# Torent_Module_75.net
KiCad netlist of a schematic drawn in EAGLE
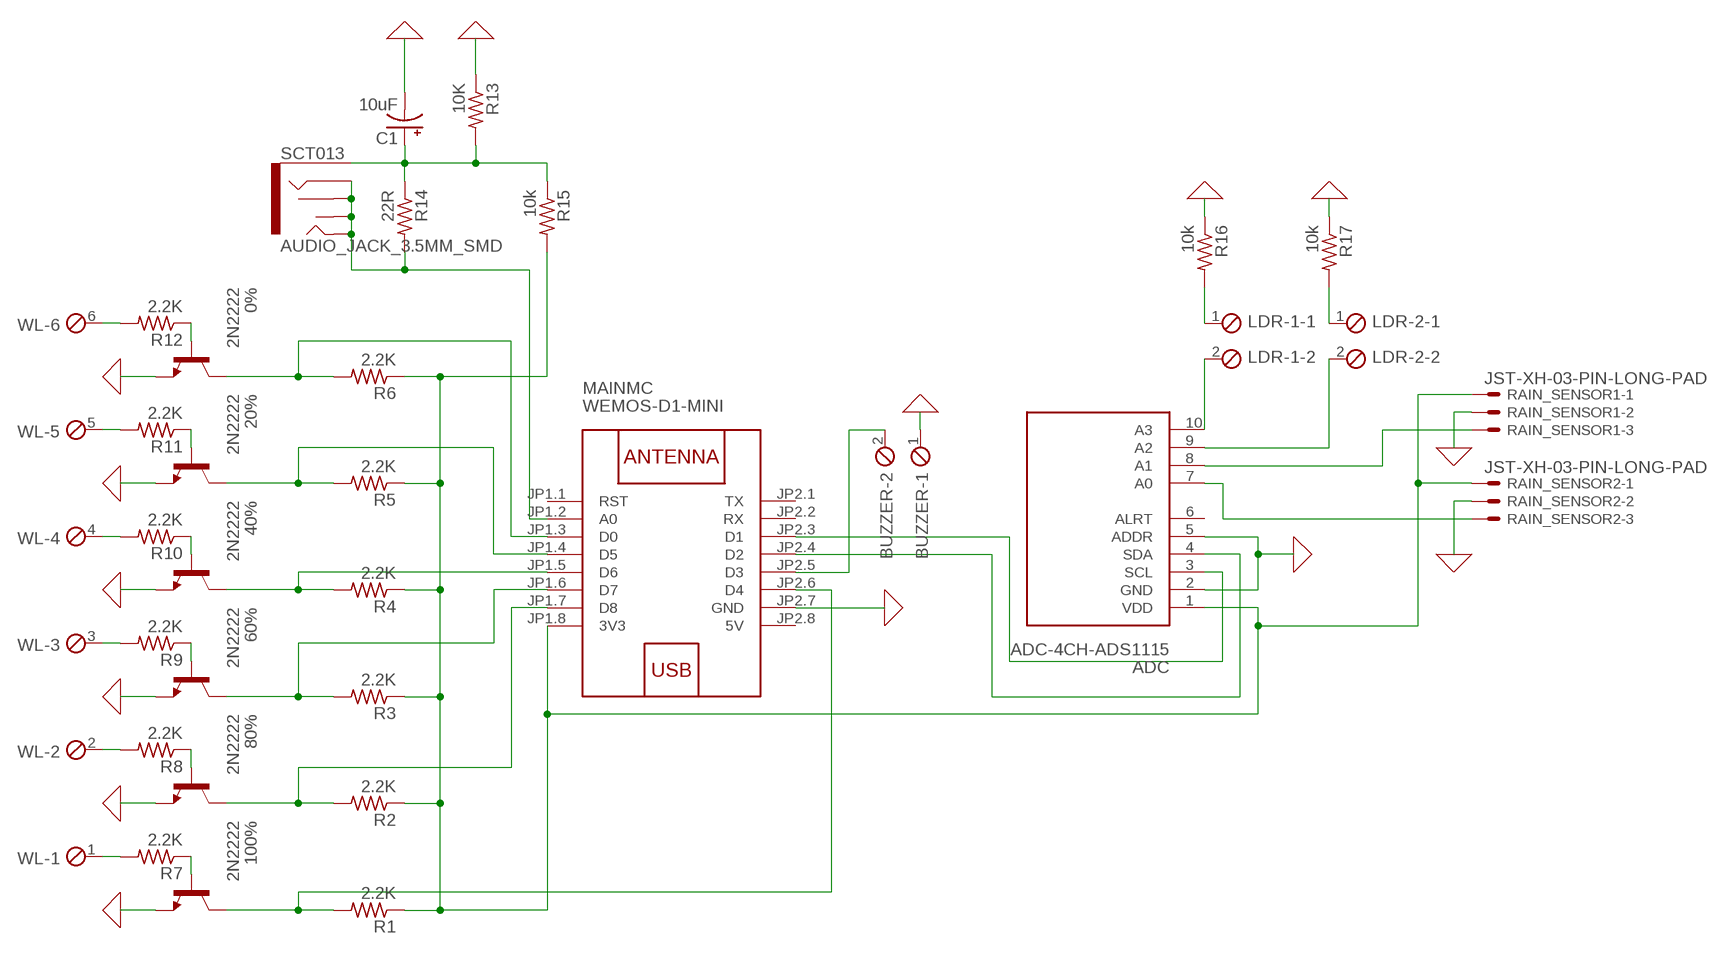
[diagram p0: schematic, sheet 1]

(export (version "E")
  (design (tool "Eeschema 10.0.6"))
  (components
    (comp (ref "0%")
      (value "2N2222")
      (footprint "eagle-import:TO92-EBC-OVAL")
      (libsource (lib "eagle-import") (part "2N2222"))
    )
    (comp (ref "20%")
      (value "2N2222")
      (footprint "eagle-import:TO92-EBC-OVAL")
      (libsource (lib "eagle-import") (part "2N2222"))
    )
    (comp (ref "40%")
      (value "2N2222")
      (footprint "eagle-import:TO92-EBC-OVAL")
      (libsource (lib "eagle-import") (part "2N2222"))
    )
    (comp (ref "60%")
      (value "2N2222")
      (footprint "eagle-import:TO92-EBC-OVAL")
      (libsource (lib "eagle-import") (part "2N2222"))
    )
    (comp (ref "80%")
      (value "2N2222")
      (footprint "eagle-import:TO92-EBC-OVAL")
      (libsource (lib "eagle-import") (part "2N2222"))
    )
    (comp (ref "100%")
      (value "2N2222")
      (footprint "eagle-import:TO92-EBC-OVAL")
      (libsource (lib "eagle-import") (part "2N2222"))
    )
    (comp (ref "ADC")
      (value "ADC-4CH-ADS1115")
      (footprint "eagle-import:ADC-4CH-ADS1115")
      (libsource (lib "eagle-import") (part "ADC-4CH-ADS1115"))
    )
    (comp (ref "BUZZER")
      (value "MPT2")
      (footprint "eagle-import:2POL254")
      (libsource (lib "eagle-import") (part "MPT2"))
    )
    (comp (ref "C1")
      (value "10uF")
      (footprint "eagle-import:TT2D7")
      (libsource (lib "eagle-import") (part "CPOL-USTT2D7"))
    )
    (comp (ref "LDR-1")
      (value "MPT2")
      (footprint "eagle-import:2POL254")
      (libsource (lib "eagle-import") (part "MPT2"))
    )
    (comp (ref "LDR-2")
      (value "MPT2")
      (footprint "eagle-import:2POL254")
      (libsource (lib "eagle-import") (part "MPT2"))
    )
    (comp (ref "MAINMC")
      (value "WEMOS-D1-MINI")
      (footprint "eagle-import:WEMOS-D1-MINI")
      (libsource (lib "eagle-import") (part "WEMOS-D1-MINI"))
    )
    (comp (ref "R1")
      (value "2.2K")
      (footprint "eagle-import:0207_9")
      (libsource (lib "eagle-import") (part "R-US_0207/9"))
    )
    (comp (ref "R2")
      (value "2.2K")
      (footprint "eagle-import:0207_9")
      (libsource (lib "eagle-import") (part "R-US_0207/9"))
    )
    (comp (ref "R3")
      (value "2.2K")
      (footprint "eagle-import:0207_9")
      (libsource (lib "eagle-import") (part "R-US_0207/9"))
    )
    (comp (ref "R4")
      (value "2.2K")
      (footprint "eagle-import:0207_9")
      (libsource (lib "eagle-import") (part "R-US_0207/9"))
    )
    (comp (ref "R5")
      (value "2.2K")
      (footprint "eagle-import:0207_9")
      (libsource (lib "eagle-import") (part "R-US_0207/9"))
    )
    (comp (ref "R6")
      (value "2.2K")
      (footprint "eagle-import:0207_9")
      (libsource (lib "eagle-import") (part "R-US_0207/9"))
    )
    (comp (ref "R7")
      (value "2.2K")
      (footprint "eagle-import:0207_9")
      (libsource (lib "eagle-import") (part "R-US_0207/9"))
    )
    (comp (ref "R8")
      (value "2.2K")
      (footprint "eagle-import:0207_9")
      (libsource (lib "eagle-import") (part "R-US_0207/9"))
    )
    (comp (ref "R9")
      (value "2.2K")
      (footprint "eagle-import:0207_9")
      (libsource (lib "eagle-import") (part "R-US_0207/9"))
    )
    (comp (ref "R10")
      (value "2.2K")
      (footprint "eagle-import:0207_9")
      (libsource (lib "eagle-import") (part "R-US_0207/9"))
    )
    (comp (ref "R11")
      (value "2.2K")
      (footprint "eagle-import:0207_9")
      (libsource (lib "eagle-import") (part "R-US_0207/9"))
    )
    (comp (ref "R12")
      (value "2.2K")
      (footprint "eagle-import:0207_9")
      (libsource (lib "eagle-import") (part "R-US_0207/9"))
    )
    (comp (ref "R13")
      (value "10K")
      (footprint "eagle-import:0207_9")
      (libsource (lib "eagle-import") (part "R-US_0207/9"))
    )
    (comp (ref "R14")
      (value "22R")
      (footprint "eagle-import:0207_9")
      (libsource (lib "eagle-import") (part "R-US_0207/9"))
    )
    (comp (ref "R15")
      (value "10k")
      (footprint "eagle-import:0207_9")
      (libsource (lib "eagle-import") (part "R-US_0207/9"))
    )
    (comp (ref "R16")
      (value "10k")
      (footprint "eagle-import:0207_9")
      (libsource (lib "eagle-import") (part "R-US_0207/9"))
    )
    (comp (ref "R17")
      (value "10k")
      (footprint "eagle-import:0207_9")
      (libsource (lib "eagle-import") (part "R-US_0207/9"))
    )
    (comp (ref "RAIN_SENSOR1")
      (value "JST-XH-03-PIN-LONG-PAD")
      (footprint "eagle-import:JST-XH-03-PACKAGE-LONG-PAD")
      (libsource (lib "eagle-import") (part "JST-XH-03-PIN-LONG-PAD"))
    )
    (comp (ref "RAIN_SENSOR2")
      (value "JST-XH-03-PIN-LONG-PAD")
      (footprint "eagle-import:JST-XH-03-PACKAGE-LONG-PAD")
      (libsource (lib "eagle-import") (part "JST-XH-03-PIN-LONG-PAD"))
    )
    (comp (ref "SCT013")
      (value "AUDIO_JACK_3.5MM_SMD")
      (footprint "eagle-import:AUDIO-JACK-3.5MM-SMD")
      (libsource (lib "eagle-import") (part "AUDIO_JACK_3.5MM_SMD"))
    )
    (comp (ref "WL")
      (value "MPT6")
      (footprint "eagle-import:6POL254")
      (libsource (lib "eagle-import") (part "MPT6"))
    )
  )
  (nets
    (net (code "1") (name "/5V") (class "Default")
      (node (ref "MAINMC") (pin "JP2.8") (pinfunction "5V_JP2.8") (pintype "power_in"))
    )
    (net (code "2") (name "GND") (class "Default")
      (node (ref "0%") (pin "E") (pinfunction "E_E") (pintype "passive"))
      (node (ref "100%") (pin "E") (pinfunction "E_E") (pintype "passive"))
      (node (ref "20%") (pin "E") (pinfunction "E_E") (pintype "passive"))
      (node (ref "40%") (pin "E") (pinfunction "E_E") (pintype "passive"))
      (node (ref "60%") (pin "E") (pinfunction "E_E") (pintype "passive"))
      (node (ref "80%") (pin "E") (pinfunction "E_E") (pintype "passive"))
      (node (ref "ADC") (pin "2") (pinfunction "GND_2") (pintype "power_in"))
      (node (ref "ADC") (pin "5") (pinfunction "ADDR_5") (pintype "bidirectional"))
      (node (ref "BUZZER") (pin "1") (pinfunction "1_1") (pintype "passive"))
      (node (ref "C1") (pin "-") (pinfunction "-_-") (pintype "passive"))
      (node (ref "MAINMC") (pin "JP2.7") (pinfunction "GND_JP2.7") (pintype "power_in"))
      (node (ref "R13") (pin "1") (pinfunction "1_1") (pintype "passive"))
      (node (ref "R16") (pin "1") (pinfunction "1_1") (pintype "passive"))
      (node (ref "R17") (pin "1") (pinfunction "1_1") (pintype "passive"))
      (node (ref "RAIN_SENSOR1") (pin "2") (pinfunction "S_2") (pintype "passive"))
      (node (ref "RAIN_SENSOR2") (pin "2") (pinfunction "S_2") (pintype "passive"))
    )
    (net (code "3") (name "Net-(0%-PadB)") (class "Default")
      (node (ref "0%") (pin "B") (pinfunction "B_B") (pintype "passive"))
      (node (ref "R12") (pin "1") (pinfunction "1_1") (pintype "passive"))
    )
    (net (code "4") (name "Net-(20%-PadB)") (class "Default")
      (node (ref "20%") (pin "B") (pinfunction "B_B") (pintype "passive"))
      (node (ref "R11") (pin "1") (pinfunction "1_1") (pintype "passive"))
    )
    (net (code "5") (name "Net-(40%-PadB)") (class "Default")
      (node (ref "40%") (pin "B") (pinfunction "B_B") (pintype "passive"))
      (node (ref "R10") (pin "1") (pinfunction "1_1") (pintype "passive"))
    )
    (net (code "6") (name "Net-(60%-PadB)") (class "Default")
      (node (ref "60%") (pin "B") (pinfunction "B_B") (pintype "passive"))
      (node (ref "R9") (pin "1") (pinfunction "1_1") (pintype "passive"))
    )
    (net (code "7") (name "Net-(80%-PadB)") (class "Default")
      (node (ref "80%") (pin "B") (pinfunction "B_B") (pintype "passive"))
      (node (ref "R8") (pin "1") (pinfunction "1_1") (pintype "passive"))
    )
    (net (code "8") (name "Net-(100%-PadB)") (class "Default")
      (node (ref "100%") (pin "B") (pinfunction "B_B") (pintype "passive"))
      (node (ref "R7") (pin "1") (pinfunction "1_1") (pintype "passive"))
    )
    (net (code "9") (name "Net-(ADC-A0)") (class "Default")
      (node (ref "ADC") (pin "7") (pinfunction "A0_7") (pintype "input"))
      (node (ref "RAIN_SENSOR2") (pin "3") (pinfunction "S_3") (pintype "passive"))
    )
    (net (code "10") (name "Net-(ADC-A1)") (class "Default")
      (node (ref "ADC") (pin "8") (pinfunction "A1_8") (pintype "input"))
      (node (ref "RAIN_SENSOR1") (pin "3") (pinfunction "S_3") (pintype "passive"))
    )
    (net (code "11") (name "Net-(ADC-A2)") (class "Default")
      (node (ref "ADC") (pin "9") (pinfunction "A2_9") (pintype "input"))
      (node (ref "LDR-2") (pin "2") (pinfunction "1_2") (pintype "passive"))
    )
    (net (code "12") (name "Net-(ADC-A3)") (class "Default")
      (node (ref "ADC") (pin "10") (pinfunction "A3_10") (pintype "input"))
      (node (ref "LDR-1") (pin "2") (pinfunction "1_2") (pintype "passive"))
    )
    (net (code "13") (name "Net-(ADC-SCL)") (class "Default")
      (node (ref "ADC") (pin "3") (pinfunction "SCL_3") (pintype "bidirectional"))
      (node (ref "MAINMC") (pin "JP2.3") (pinfunction "D1_JP2.3") (pintype "bidirectional"))
    )
    (net (code "14") (name "Net-(ADC-SDA)") (class "Default")
      (node (ref "ADC") (pin "4") (pinfunction "SDA_4") (pintype "bidirectional"))
      (node (ref "MAINMC") (pin "JP2.4") (pinfunction "D2_JP2.4") (pintype "bidirectional"))
    )
    (net (code "15") (name "Net-(ADC-VDD)") (class "Default")
      (node (ref "ADC") (pin "1") (pinfunction "VDD_1") (pintype "power_in"))
      (node (ref "MAINMC") (pin "JP1.8") (pinfunction "3V3_JP1.8") (pintype "power_in"))
      (node (ref "R1") (pin "1") (pinfunction "1_1") (pintype "passive"))
      (node (ref "R15") (pin "2") (pinfunction "2_2") (pintype "passive"))
      (node (ref "R2") (pin "1") (pinfunction "1_1") (pintype "passive"))
      (node (ref "R3") (pin "1") (pinfunction "1_1") (pintype "passive"))
      (node (ref "R4") (pin "1") (pinfunction "1_1") (pintype "passive"))
      (node (ref "R5") (pin "1") (pinfunction "1_1") (pintype "passive"))
      (node (ref "R6") (pin "1") (pinfunction "1_1") (pintype "passive"))
      (node (ref "RAIN_SENSOR1") (pin "1") (pinfunction "S_1") (pintype "passive"))
      (node (ref "RAIN_SENSOR2") (pin "1") (pinfunction "S_1") (pintype "passive"))
    )
    (net (code "16") (name "Net-(BUZZERB-1)") (class "Default")
      (node (ref "BUZZER") (pin "2") (pinfunction "1_2") (pintype "passive"))
      (node (ref "MAINMC") (pin "JP2.5") (pinfunction "D3_JP2.5") (pintype "bidirectional"))
    )
    (net (code "17") (name "Net-(C1-Pad+)") (class "Default")
      (node (ref "C1") (pin "+") (pinfunction "+_+") (pintype "passive"))
      (node (ref "R13") (pin "2") (pinfunction "2_2") (pintype "passive"))
      (node (ref "R14") (pin "1") (pinfunction "1_1") (pintype "passive"))
      (node (ref "R15") (pin "1") (pinfunction "1_1") (pintype "passive"))
      (node (ref "SCT013") (pin "SLEEVE") (pinfunction "SLEEVE_SLEEVE") (pintype "bidirectional"))
    )
    (net (code "18") (name "Net-(LDR-1-Pad1)") (class "Default")
      (node (ref "LDR-1") (pin "1") (pinfunction "1_1") (pintype "passive"))
      (node (ref "R16") (pin "2") (pinfunction "2_2") (pintype "passive"))
    )
    (net (code "19") (name "Net-(LDR-2-Pad1)") (class "Default")
      (node (ref "LDR-2") (pin "1") (pinfunction "1_1") (pintype "passive"))
      (node (ref "R17") (pin "2") (pinfunction "2_2") (pintype "passive"))
    )
    (net (code "20") (name "Net-(MAINMC-A0)") (class "Default")
      (node (ref "MAINMC") (pin "JP1.2") (pinfunction "A0_JP1.2") (pintype "bidirectional"))
      (node (ref "R14") (pin "2") (pinfunction "2_2") (pintype "passive"))
      (node (ref "SCT013") (pin "RING") (pinfunction "RING_RING") (pintype "bidirectional"))
      (node (ref "SCT013") (pin "RSH") (pinfunction "RSH_RSH") (pintype "bidirectional"))
      (node (ref "SCT013") (pin "TIP") (pinfunction "TIP_TIP") (pintype "bidirectional"))
      (node (ref "SCT013") (pin "TSH") (pinfunction "TSH_TSH") (pintype "bidirectional"))
    )
    (net (code "21") (name "Net-(MAINMC-D0)") (class "Default")
      (node (ref "0%") (pin "C") (pinfunction "C_C") (pintype "passive"))
      (node (ref "MAINMC") (pin "JP1.3") (pinfunction "D0_JP1.3") (pintype "bidirectional"))
      (node (ref "R6") (pin "2") (pinfunction "2_2") (pintype "passive"))
    )
    (net (code "22") (name "Net-(MAINMC-D4)") (class "Default")
      (node (ref "100%") (pin "C") (pinfunction "C_C") (pintype "passive"))
      (node (ref "MAINMC") (pin "JP2.6") (pinfunction "D4_JP2.6") (pintype "bidirectional"))
      (node (ref "R1") (pin "2") (pinfunction "2_2") (pintype "passive"))
    )
    (net (code "23") (name "Net-(MAINMC-D5)") (class "Default")
      (node (ref "20%") (pin "C") (pinfunction "C_C") (pintype "passive"))
      (node (ref "MAINMC") (pin "JP1.4") (pinfunction "D5_JP1.4") (pintype "bidirectional"))
      (node (ref "R5") (pin "2") (pinfunction "2_2") (pintype "passive"))
    )
    (net (code "24") (name "Net-(MAINMC-D6)") (class "Default")
      (node (ref "40%") (pin "C") (pinfunction "C_C") (pintype "passive"))
      (node (ref "MAINMC") (pin "JP1.5") (pinfunction "D6_JP1.5") (pintype "bidirectional"))
      (node (ref "R4") (pin "2") (pinfunction "2_2") (pintype "passive"))
    )
    (net (code "25") (name "Net-(MAINMC-D7)") (class "Default")
      (node (ref "60%") (pin "C") (pinfunction "C_C") (pintype "passive"))
      (node (ref "MAINMC") (pin "JP1.6") (pinfunction "D7_JP1.6") (pintype "bidirectional"))
      (node (ref "R3") (pin "2") (pinfunction "2_2") (pintype "passive"))
    )
    (net (code "26") (name "Net-(MAINMC-D8)") (class "Default")
      (node (ref "80%") (pin "C") (pinfunction "C_C") (pintype "passive"))
      (node (ref "MAINMC") (pin "JP1.7") (pinfunction "D8_JP1.7") (pintype "bidirectional"))
      (node (ref "R2") (pin "2") (pinfunction "2_2") (pintype "passive"))
    )
    (net (code "27") (name "Net-(R7-Pad2)") (class "Default")
      (node (ref "R7") (pin "2") (pinfunction "2_2") (pintype "passive"))
      (node (ref "WL") (pin "1") (pinfunction "1_1") (pintype "passive"))
    )
    (net (code "28") (name "Net-(WLB-1)") (class "Default")
      (node (ref "R8") (pin "2") (pinfunction "2_2") (pintype "passive"))
      (node (ref "WL") (pin "2") (pinfunction "1_2") (pintype "passive"))
    )
    (net (code "29") (name "Net-(WLC-1)") (class "Default")
      (node (ref "R9") (pin "2") (pinfunction "2_2") (pintype "passive"))
      (node (ref "WL") (pin "3") (pinfunction "1_3") (pintype "passive"))
    )
    (net (code "30") (name "Net-(WLD-1)") (class "Default")
      (node (ref "R10") (pin "2") (pinfunction "2_2") (pintype "passive"))
      (node (ref "WL") (pin "4") (pinfunction "1_4") (pintype "passive"))
    )
    (net (code "31") (name "Net-(WLE-1)") (class "Default")
      (node (ref "R11") (pin "2") (pinfunction "2_2") (pintype "passive"))
      (node (ref "WL") (pin "5") (pinfunction "1_5") (pintype "passive"))
    )
    (net (code "32") (name "Net-(WLF-1)") (class "Default")
      (node (ref "R12") (pin "2") (pinfunction "2_2") (pintype "passive"))
      (node (ref "WL") (pin "6") (pinfunction "1_6") (pintype "passive"))
    )
    (net (code "33") (name "unconnected-(ADC-ALRT-Pad6)") (class "Default")
      (node (ref "ADC") (pin "6") (pinfunction "ALRT_6") (pintype "bidirectional"))
    )
    (net (code "34") (name "unconnected-(MAINMC-RST-PadJP1.1)") (class "Default")
      (node (ref "MAINMC") (pin "JP1.1") (pinfunction "RST_JP1.1") (pintype "bidirectional"))
    )
    (net (code "35") (name "unconnected-(MAINMC-RX-PadJP2.2)") (class "Default")
      (node (ref "MAINMC") (pin "JP2.2") (pinfunction "RX_JP2.2") (pintype "bidirectional"))
    )
    (net (code "36") (name "unconnected-(MAINMC-TX-PadJP2.1)") (class "Default")
      (node (ref "MAINMC") (pin "JP2.1") (pinfunction "TX_JP2.1") (pintype "bidirectional"))
    )
  )
)
